# mag_pos.net
KiCad netlist of a schematic drawn in Altium Designer
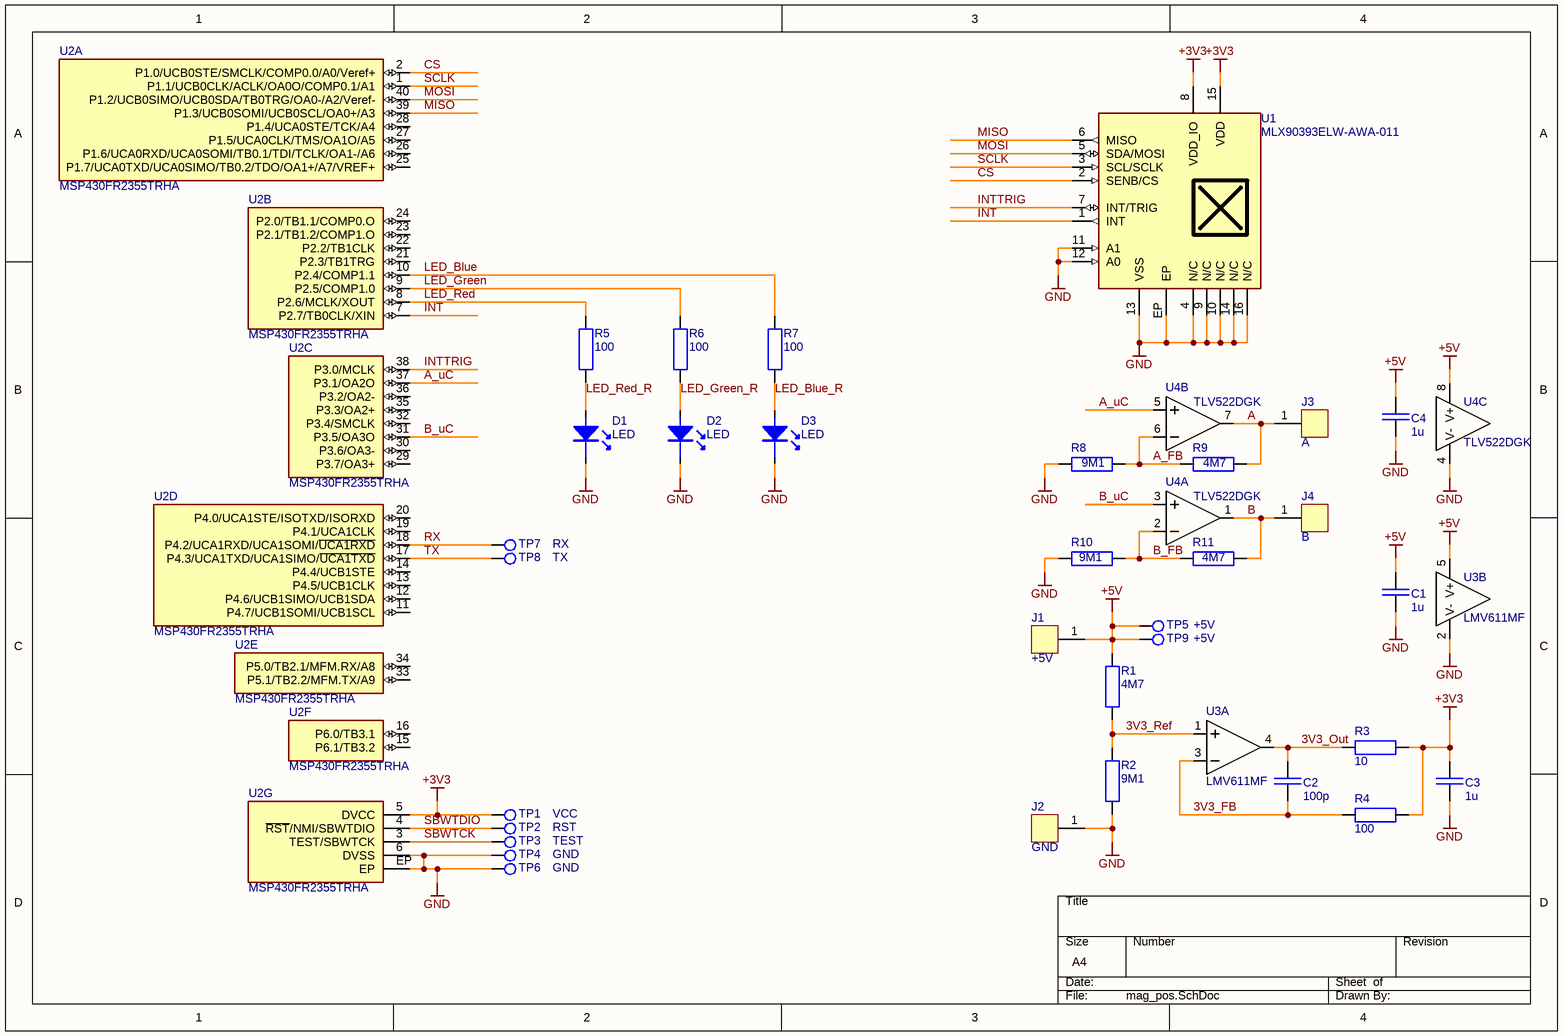
[diagram p0: mag_pos.SchDoc]

(export (version "E")
  (design (tool "Eeschema 10.0.6"))
  (components
    (comp (ref "C1")
      (value "1u")
      (footprint "AHO_Altium_Lib:C_0603_S")
      (libsource (lib "AHO_Altium_Lib") (part "C"))
    )
    (comp (ref "C2")
      (value "100p")
      (footprint "AHO_Altium_Lib:C_0603_S")
      (libsource (lib "AHO_Altium_Lib") (part "C"))
    )
    (comp (ref "C3")
      (value "1u")
      (footprint "AHO_Altium_Lib:C_0603_S")
      (libsource (lib "AHO_Altium_Lib") (part "C"))
    )
    (comp (ref "C4")
      (value "1u")
      (footprint "AHO_Altium_Lib:C_0603_S")
      (libsource (lib "AHO_Altium_Lib") (part "C"))
    )
    (comp (ref "D1")
      (value "LED")
      (footprint "LED_0603_S_RED")
      (libsource (lib "AHO_Altium_Lib") (part "LED"))
    )
    (comp (ref "D2")
      (value "LED")
      (footprint "LED_0603_S_GREEN")
      (libsource (lib "AHO_Altium_Lib") (part "LED"))
    )
    (comp (ref "D3")
      (value "LED")
      (footprint "LED_0603_S_BLUE")
      (libsource (lib "AHO_Altium_Lib") (part "LED"))
    )
    (comp (ref "J1")
      (value "+5V")
      (footprint "mag_pos:WIRE_1MM_1.5MM_THT")
      (description "1mm Wire")
      (libsource (lib "") (part "Wire_1MM_1"))
    )
    (comp (ref "J2")
      (value "GND")
      (footprint "mag_pos:WIRE_1MM_1.5MM_THT")
      (description "1mm Wire")
      (libsource (lib "") (part "Wire_1MM_1"))
    )
    (comp (ref "J3")
      (value "A")
      (footprint "mag_pos:WIRE_1MM_1.5MM_THT")
      (description "1mm Wire")
      (libsource (lib "mag_pos") (part "Wire_1MM"))
    )
    (comp (ref "J4")
      (value "B")
      (footprint "mag_pos:WIRE_1MM_1.5MM_THT")
      (description "1mm Wire")
      (libsource (lib "mag_pos") (part "Wire_1MM"))
    )
    (comp (ref "R1")
      (value "4M7")
      (footprint "AHO_Altium_Lib:R_0603_S")
      (description "Normaler Widerstand")
      (libsource (lib "AHO_Altium_Lib") (part "R"))
    )
    (comp (ref "R2")
      (value "9M1")
      (footprint "AHO_Altium_Lib:R_0603_S")
      (description "Normaler Widerstand")
      (libsource (lib "AHO_Altium_Lib") (part "R"))
    )
    (comp (ref "R3")
      (value "10")
      (footprint "AHO_Altium_Lib:R_0603_S")
      (description "Normaler Widerstand")
      (libsource (lib "AHO_Altium_Lib") (part "R"))
    )
    (comp (ref "R4")
      (value "100")
      (footprint "AHO_Altium_Lib:R_0603_S")
      (description "Normaler Widerstand")
      (libsource (lib "AHO_Altium_Lib") (part "R"))
    )
    (comp (ref "R5")
      (value "100")
      (footprint "AHO_Altium_Lib:R_0603_S")
      (description "Normaler Widerstand")
      (libsource (lib "AHO_Altium_Lib") (part "R"))
    )
    (comp (ref "R6")
      (value "100")
      (footprint "AHO_Altium_Lib:R_0603_S")
      (description "Normaler Widerstand")
      (libsource (lib "AHO_Altium_Lib") (part "R"))
    )
    (comp (ref "R7")
      (value "100")
      (footprint "AHO_Altium_Lib:R_0603_S")
      (description "Normaler Widerstand")
      (libsource (lib "AHO_Altium_Lib") (part "R"))
    )
    (comp (ref "R8")
      (value "9M1")
      (footprint "AHO_Altium_Lib:R_0603_S")
      (description "Normaler Widerstand")
      (libsource (lib "AHO_Altium_Lib") (part "R"))
    )
    (comp (ref "R9")
      (value "4M7")
      (footprint "AHO_Altium_Lib:R_0603_S")
      (description "Normaler Widerstand")
      (libsource (lib "AHO_Altium_Lib") (part "R"))
    )
    (comp (ref "R10")
      (value "9M1")
      (footprint "AHO_Altium_Lib:R_0603_S")
      (description "Normaler Widerstand")
      (libsource (lib "AHO_Altium_Lib") (part "R"))
    )
    (comp (ref "R11")
      (value "4M7")
      (footprint "AHO_Altium_Lib:R_0603_S")
      (description "Normaler Widerstand")
      (libsource (lib "AHO_Altium_Lib") (part "R"))
    )
    (comp (ref "TP1")
      (value "VCC")
      (footprint "mag_pos:TP_SMD_1MM")
      (description "Testpoint SMD 1mm")
      (libsource (lib "mag_pos") (part "TP_SMD_1mm"))
    )
    (comp (ref "TP2")
      (value "RST")
      (footprint "mag_pos:TP_SMD_1MM")
      (description "Testpoint SMD 1mm")
      (libsource (lib "mag_pos") (part "TP_SMD_1mm"))
    )
    (comp (ref "TP3")
      (value "TEST")
      (footprint "mag_pos:TP_SMD_1MM")
      (description "Testpoint SMD 1mm")
      (libsource (lib "mag_pos") (part "TP_SMD_1mm"))
    )
    (comp (ref "TP4")
      (value "GND")
      (footprint "mag_pos:TP_SMD_1MM")
      (description "Testpoint SMD 1mm")
      (libsource (lib "mag_pos") (part "TP_SMD_1mm"))
    )
    (comp (ref "TP5")
      (value "+5V")
      (footprint "mag_pos:TP_SMD_1MM")
      (description "Testpoint SMD 1mm")
      (libsource (lib "mag_pos") (part "TP_SMD_1mm"))
    )
    (comp (ref "TP6")
      (value "GND")
      (footprint "mag_pos:TP_SMD_1MM")
      (description "Testpoint SMD 1mm")
      (libsource (lib "mag_pos") (part "TP_SMD_1mm"))
    )
    (comp (ref "TP7")
      (value "RX")
      (footprint "mag_pos:TP_SMD_1MM")
      (description "Testpoint SMD 1mm")
      (libsource (lib "mag_pos") (part "TP_SMD_1mm"))
    )
    (comp (ref "TP8")
      (value "TX")
      (footprint "mag_pos:TP_SMD_1MM")
      (description "Testpoint SMD 1mm")
      (libsource (lib "mag_pos") (part "TP_SMD_1mm"))
    )
    (comp (ref "TP9")
      (value "+5V")
      (footprint "mag_pos:TP_SMD_1MM")
      (description "Testpoint SMD 1mm")
      (libsource (lib "mag_pos") (part "TP_SMD_1mm"))
    )
    (comp (ref "U1")
      (value "MLX90393ELW-AWA-011")
      (footprint "mag_pos:QFN50P300X300X100-16")
      (description "Triaxis Magnetic Node, QFN16")
      (libsource (lib "mag_pos") (part "MLX90393ELW-AWA-011"))
    )
    (comp (ref "U2")
      (value "MSP430FR2355TRHA")
      (footprint "mag_pos:QFN50P600X600X100-40")
      (description "Mixed-Signal Microcontroller, 16Bit, 32kB FRAM, 4kB SRAM, QFN40")
      (libsource (lib "mag_pos") (part "MSP430FR2355TRHA"))
    )
    (comp (ref "U3")
      (value "LMV611MF")
      (footprint "mag_pos:SOT23-5_1.45")
      (description "LMV611 SOT-23-5 Single, 1.4-MHz, Low-Power, General-Purpose 1.8-V Operational Amplifier")
      (fields (field (name "MANUFACTURER") "TI"))
      (libsource (lib "mag_pos") (part "LMV611MF"))
    )
    (comp (ref "U4")
      (value "TLV522DGK")
      (footprint "mag_pos:SOP65P500X300X110-8")
      (description "TLV522 VSSOP-8 Dual Nanopower, 500nA, RRIO CMOS Operational Amplifier")
      (fields (field (name "MANUFACTURER") "TI"))
      (libsource (lib "mag_pos") (part "TLV522DGK"))
    )
  )
  (nets
    (net (code "1") (name "+3V3") (class "Default")
      (node (ref "C3") (pin "1") (pinfunction "1_1") (pintype "passive"))
      (node (ref "R3") (pin "2") (pintype "passive"))
      (node (ref "R4") (pin "2") (pintype "passive"))
      (node (ref "TP1") (pin "1") (pinfunction "1_1") (pintype "passive"))
      (node (ref "U1") (pin "15") (pinfunction "VDD_15") (pintype "power_in"))
      (node (ref "U1") (pin "8") (pinfunction "VDD_IO_8") (pintype "power_in"))
      (node (ref "U2") (pin "5") (pinfunction "DVCC_5") (pintype "power_in"))
    )
    (net (code "2") (name "+5V") (class "Default")
      (node (ref "C1") (pin "1") (pinfunction "1_1") (pintype "passive"))
      (node (ref "C4") (pin "1") (pinfunction "1_1") (pintype "passive"))
      (node (ref "J1") (pin "1") (pinfunction "1_1") (pintype "passive"))
      (node (ref "R1") (pin "1") (pintype "passive"))
      (node (ref "TP5") (pin "1") (pinfunction "1_1") (pintype "passive"))
      (node (ref "TP9") (pin "1") (pinfunction "1_1") (pintype "passive"))
      (node (ref "U3") (pin "5") (pinfunction "V+_5") (pintype "passive"))
      (node (ref "U4") (pin "8") (pinfunction "V+_8") (pintype "passive"))
    )
    (net (code "3") (name "/3V3_FB") (class "Default")
      (node (ref "C2") (pin "2") (pinfunction "2_2") (pintype "passive"))
      (node (ref "R4") (pin "1") (pintype "passive"))
      (node (ref "U3") (pin "3") (pinfunction "-IN_3") (pintype "passive"))
    )
    (net (code "4") (name "/3V3_Out") (class "Default")
      (node (ref "C2") (pin "1") (pinfunction "1_1") (pintype "passive"))
      (node (ref "R3") (pin "1") (pintype "passive"))
      (node (ref "U3") (pin "4") (pinfunction "4_4") (pintype "passive"))
    )
    (net (code "5") (name "/3V3_Ref") (class "Default")
      (node (ref "R1") (pin "2") (pintype "passive"))
      (node (ref "R2") (pin "1") (pintype "passive"))
      (node (ref "U3") (pin "1") (pinfunction "+IN_1") (pintype "passive"))
    )
    (net (code "6") (name "/A") (class "Default")
      (node (ref "J3") (pin "1") (pinfunction "1_1") (pintype "passive"))
      (node (ref "R9") (pin "1") (pintype "passive"))
      (node (ref "U4") (pin "7") (pinfunction "Out_7") (pintype "passive"))
    )
    (net (code "7") (name "/A_FB") (class "Default")
      (node (ref "R8") (pin "1") (pintype "passive"))
      (node (ref "R9") (pin "2") (pintype "passive"))
      (node (ref "U4") (pin "6") (pinfunction "-IN_6") (pintype "passive"))
    )
    (net (code "8") (name "/A_uC") (class "Default")
      (node (ref "U2") (pin "37") (pinfunction "P3.1/OA2O_37") (pintype "bidirectional"))
      (node (ref "U4") (pin "5") (pinfunction "+IN_5") (pintype "passive"))
    )
    (net (code "9") (name "/B") (class "Default")
      (node (ref "J4") (pin "1") (pinfunction "1_1") (pintype "passive"))
      (node (ref "R11") (pin "1") (pintype "passive"))
      (node (ref "U4") (pin "1") (pinfunction "Out_1") (pintype "passive"))
    )
    (net (code "10") (name "/B_FB") (class "Default")
      (node (ref "R10") (pin "1") (pintype "passive"))
      (node (ref "R11") (pin "2") (pintype "passive"))
      (node (ref "U4") (pin "2") (pinfunction "-IN_2") (pintype "passive"))
    )
    (net (code "11") (name "/B_uC") (class "Default")
      (node (ref "U2") (pin "31") (pinfunction "P3.5/OA3O_31") (pintype "bidirectional"))
      (node (ref "U4") (pin "3") (pinfunction "+IN_3") (pintype "passive"))
    )
    (net (code "12") (name "/CS") (class "Default")
      (node (ref "U1") (pin "2") (pinfunction "SENB/CS_2") (pintype "input"))
      (node (ref "U2") (pin "2") (pinfunction "P1.0/UCB0STE/SMCLK/COMP0.0/A0/Veref+_2") (pintype "bidirectional"))
    )
    (net (code "13") (name "/INT") (class "Default")
      (node (ref "U1") (pin "1") (pinfunction "INT_1") (pintype "output"))
      (node (ref "U2") (pin "7") (pinfunction "P2.7/TB0CLK/XIN_7") (pintype "bidirectional"))
    )
    (net (code "14") (name "/INTTRIG") (class "Default")
      (node (ref "U1") (pin "7") (pinfunction "INT/TRIG_7") (pintype "bidirectional"))
      (node (ref "U2") (pin "38") (pinfunction "P3.0/MCLK_38") (pintype "bidirectional"))
    )
    (net (code "15") (name "/LED_Blue") (class "Default")
      (node (ref "R7") (pin "2") (pintype "passive"))
      (node (ref "U2") (pin "10") (pinfunction "P2.4/COMP1.1_10") (pintype "bidirectional"))
    )
    (net (code "16") (name "/LED_Blue_R") (class "Default")
      (node (ref "D3") (pin "A") (pinfunction "A_A") (pintype "passive"))
      (node (ref "R7") (pin "1") (pintype "passive"))
    )
    (net (code "17") (name "/LED_Green") (class "Default")
      (node (ref "R6") (pin "2") (pintype "passive"))
      (node (ref "U2") (pin "9") (pinfunction "P2.5/COMP1.0_9") (pintype "bidirectional"))
    )
    (net (code "18") (name "/LED_Green_R") (class "Default")
      (node (ref "D2") (pin "A") (pinfunction "A_A") (pintype "passive"))
      (node (ref "R6") (pin "1") (pintype "passive"))
    )
    (net (code "19") (name "/LED_Red") (class "Default")
      (node (ref "R5") (pin "2") (pintype "passive"))
      (node (ref "U2") (pin "8") (pinfunction "P2.6/MCLK/XOUT_8") (pintype "bidirectional"))
    )
    (net (code "20") (name "/LED_Red_R") (class "Default")
      (node (ref "D1") (pin "A") (pinfunction "A_A") (pintype "passive"))
      (node (ref "R5") (pin "1") (pintype "passive"))
    )
    (net (code "21") (name "/MISO") (class "Default")
      (node (ref "U1") (pin "6") (pinfunction "MISO_6") (pintype "output"))
      (node (ref "U2") (pin "39") (pinfunction "P1.3/UCB0SOMI/UCB0SCL/OA0+/A3_39") (pintype "bidirectional"))
    )
    (net (code "22") (name "/MOSI") (class "Default")
      (node (ref "U1") (pin "5") (pinfunction "SDA/MOSI_5") (pintype "bidirectional"))
      (node (ref "U2") (pin "40") (pinfunction "P1.2/UCB0SIMO/UCB0SDA/TB0TRG/OA0-/A2/Veref-_40") (pintype "bidirectional"))
    )
    (net (code "23") (name "/RX") (class "Default")
      (node (ref "TP7") (pin "1") (pinfunction "1_1") (pintype "passive"))
      (node (ref "U2") (pin "18") (pinfunction "P4.2/UCA1RXD/UCA1SOMI/~{UCA1RXD}_18") (pintype "bidirectional"))
    )
    (net (code "24") (name "/SBWTCK") (class "Default")
      (node (ref "TP3") (pin "1") (pinfunction "1_1") (pintype "passive"))
      (node (ref "U2") (pin "3") (pinfunction "TEST/SBWTCK_3") (pintype "power_in"))
    )
    (net (code "25") (name "/SBWTDIO") (class "Default")
      (node (ref "TP2") (pin "1") (pinfunction "1_1") (pintype "passive"))
      (node (ref "U2") (pin "4") (pinfunction "~{RST}/NMI/SBWTDIO_4") (pintype "power_in"))
    )
    (net (code "26") (name "/SCLK") (class "Default")
      (node (ref "U1") (pin "3") (pinfunction "SCL/SCLK_3") (pintype "input"))
      (node (ref "U2") (pin "1") (pinfunction "P1.1/UCB0CLK/ACLK/OA0O/COMP0.1/A1_1") (pintype "bidirectional"))
    )
    (net (code "27") (name "/TX") (class "Default")
      (node (ref "TP8") (pin "1") (pinfunction "1_1") (pintype "passive"))
      (node (ref "U2") (pin "17") (pinfunction "P4.3/UCA1TXD/UCA1SIMO/~{UCA1TXD}_17") (pintype "bidirectional"))
    )
    (net (code "28") (name "GND") (class "Default")
      (node (ref "C1") (pin "2") (pinfunction "2_2") (pintype "passive"))
      (node (ref "C3") (pin "2") (pinfunction "2_2") (pintype "passive"))
      (node (ref "C4") (pin "2") (pinfunction "2_2") (pintype "passive"))
      (node (ref "D1") (pin "K") (pinfunction "K_K") (pintype "passive"))
      (node (ref "D2") (pin "K") (pinfunction "K_K") (pintype "passive"))
      (node (ref "D3") (pin "K") (pinfunction "K_K") (pintype "passive"))
      (node (ref "J2") (pin "1") (pinfunction "1_1") (pintype "passive"))
      (node (ref "R10") (pin "2") (pintype "passive"))
      (node (ref "R2") (pin "2") (pintype "passive"))
      (node (ref "R8") (pin "2") (pintype "passive"))
      (node (ref "TP4") (pin "1") (pinfunction "1_1") (pintype "passive"))
      (node (ref "TP6") (pin "1") (pinfunction "1_1") (pintype "passive"))
      (node (ref "U1") (pin "10") (pinfunction "N/C_10") (pintype "passive"))
      (node (ref "U1") (pin "11") (pinfunction "A1_11") (pintype "input"))
      (node (ref "U1") (pin "12") (pinfunction "A0_12") (pintype "input"))
      (node (ref "U1") (pin "13") (pinfunction "VSS_13") (pintype "power_in"))
      (node (ref "U1") (pin "14") (pinfunction "N/C_14") (pintype "passive"))
      (node (ref "U1") (pin "16") (pinfunction "N/C_16") (pintype "passive"))
      (node (ref "U1") (pin "4") (pinfunction "N/C_4") (pintype "passive"))
      (node (ref "U1") (pin "9") (pinfunction "N/C_9") (pintype "passive"))
      (node (ref "U1") (pin "EP") (pinfunction "EP_EP") (pintype "passive"))
      (node (ref "U2") (pin "6") (pinfunction "DVSS_6") (pintype "power_in"))
      (node (ref "U2") (pin "EP") (pinfunction "EP_EP") (pintype "power_in"))
      (node (ref "U3") (pin "2") (pinfunction "V-_2") (pintype "passive"))
      (node (ref "U4") (pin "4") (pinfunction "V-_4") (pintype "passive"))
    )
    (net (code "29") (name "unconnected-(U2A-P1.4{slash}UCA0STE{slash}TCK{slash}A4-Pad28)") (class "Default")
      (node (ref "U2") (pin "28") (pinfunction "P1.4/UCA0STE/TCK/A4_28") (pintype "bidirectional"))
    )
    (net (code "30") (name "unconnected-(U2A-P1.5{slash}UCA0CLK{slash}TMS{slash}OA1O{slash}A5-Pad27)") (class "Default")
      (node (ref "U2") (pin "27") (pinfunction "P1.5/UCA0CLK/TMS/OA1O/A5_27") (pintype "bidirectional"))
    )
    (net (code "31") (name "unconnected-(U2A-P1.6{slash}UCA0RXD{slash}UCA0SOMI{slash}TB0.1{slash}TDI{slash}TCLK{slash}OA1-{slash}A6-Pad26)") (class "Default")
      (node (ref "U2") (pin "26") (pinfunction "P1.6/UCA0RXD/UCA0SOMI/TB0.1/TDI/TCLK/OA1-/A6_26") (pintype "bidirectional"))
    )
    (net (code "32") (name "unconnected-(U2A-P1.7{slash}UCA0TXD{slash}UCA0SIMO{slash}TB0.2{slash}TDO{slash}OA1+{slash}A7{slash}VREF+-Pad25)") (class "Default")
      (node (ref "U2") (pin "25") (pinfunction "P1.7/UCA0TXD/UCA0SIMO/TB0.2/TDO/OA1+/A7/VREF+_25") (pintype "bidirectional"))
    )
    (net (code "33") (name "unconnected-(U2B-P2.0{slash}TB1.1{slash}COMP0.O-Pad24)") (class "Default")
      (node (ref "U2") (pin "24") (pinfunction "P2.0/TB1.1/COMP0.O_24") (pintype "bidirectional"))
    )
    (net (code "34") (name "unconnected-(U2B-P2.1{slash}TB1.2{slash}COMP1.O-Pad23)") (class "Default")
      (node (ref "U2") (pin "23") (pinfunction "P2.1/TB1.2/COMP1.O_23") (pintype "bidirectional"))
    )
    (net (code "35") (name "unconnected-(U2B-P2.2{slash}TB1CLK-Pad22)") (class "Default")
      (node (ref "U2") (pin "22") (pinfunction "P2.2/TB1CLK_22") (pintype "bidirectional"))
    )
    (net (code "36") (name "unconnected-(U2B-P2.3{slash}TB1TRG-Pad21)") (class "Default")
      (node (ref "U2") (pin "21") (pinfunction "P2.3/TB1TRG_21") (pintype "bidirectional"))
    )
    (net (code "37") (name "unconnected-(U2C-P3.2{slash}OA2--Pad36)") (class "Default")
      (node (ref "U2") (pin "36") (pinfunction "P3.2/OA2-_36") (pintype "bidirectional"))
    )
    (net (code "38") (name "unconnected-(U2C-P3.3{slash}OA2+-Pad35)") (class "Default")
      (node (ref "U2") (pin "35") (pinfunction "P3.3/OA2+_35") (pintype "bidirectional"))
    )
    (net (code "39") (name "unconnected-(U2C-P3.4{slash}SMCLK-Pad32)") (class "Default")
      (node (ref "U2") (pin "32") (pinfunction "P3.4/SMCLK_32") (pintype "bidirectional"))
    )
    (net (code "40") (name "unconnected-(U2C-P3.6{slash}OA3--Pad30)") (class "Default")
      (node (ref "U2") (pin "30") (pinfunction "P3.6/OA3-_30") (pintype "bidirectional"))
    )
    (net (code "41") (name "unconnected-(U2C-P3.7{slash}OA3+-Pad29)") (class "Default")
      (node (ref "U2") (pin "29") (pinfunction "P3.7/OA3+_29") (pintype "bidirectional"))
    )
    (net (code "42") (name "unconnected-(U2D-P4.0{slash}UCA1STE{slash}ISOTXD{slash}ISORXD-Pad20)") (class "Default")
      (node (ref "U2") (pin "20") (pinfunction "P4.0/UCA1STE/ISOTXD/ISORXD_20") (pintype "bidirectional"))
    )
    (net (code "43") (name "unconnected-(U2D-P4.1{slash}UCA1CLK-Pad19)") (class "Default")
      (node (ref "U2") (pin "19") (pinfunction "P4.1/UCA1CLK_19") (pintype "bidirectional"))
    )
    (net (code "44") (name "unconnected-(U2D-P4.4{slash}UCB1STE-Pad14)") (class "Default")
      (node (ref "U2") (pin "14") (pinfunction "P4.4/UCB1STE_14") (pintype "bidirectional"))
    )
    (net (code "45") (name "unconnected-(U2D-P4.5{slash}UCB1CLK-Pad13)") (class "Default")
      (node (ref "U2") (pin "13") (pinfunction "P4.5/UCB1CLK_13") (pintype "bidirectional"))
    )
    (net (code "46") (name "unconnected-(U2D-P4.6{slash}UCB1SIMO{slash}UCB1SDA-Pad12)") (class "Default")
      (node (ref "U2") (pin "12") (pinfunction "P4.6/UCB1SIMO/UCB1SDA_12") (pintype "bidirectional"))
    )
    (net (code "47") (name "unconnected-(U2D-P4.7{slash}UCB1SOMI{slash}UCB1SCL-Pad11)") (class "Default")
      (node (ref "U2") (pin "11") (pinfunction "P4.7/UCB1SOMI/UCB1SCL_11") (pintype "bidirectional"))
    )
    (net (code "48") (name "unconnected-(U2E-P5.0{slash}TB2.1{slash}MFM.RX{slash}A8-Pad34)") (class "Default")
      (node (ref "U2") (pin "34") (pinfunction "P5.0/TB2.1/MFM.RX/A8_34") (pintype "bidirectional"))
    )
    (net (code "49") (name "unconnected-(U2E-P5.1{slash}TB2.2{slash}MFM.TX{slash}A9-Pad33)") (class "Default")
      (node (ref "U2") (pin "33") (pinfunction "P5.1/TB2.2/MFM.TX/A9_33") (pintype "bidirectional"))
    )
    (net (code "50") (name "unconnected-(U2F-P6.0{slash}TB3.1-Pad16)") (class "Default")
      (node (ref "U2") (pin "16") (pinfunction "P6.0/TB3.1_16") (pintype "bidirectional"))
    )
    (net (code "51") (name "unconnected-(U2F-P6.1{slash}TB3.2-Pad15)") (class "Default")
      (node (ref "U2") (pin "15") (pinfunction "P6.1/TB3.2_15") (pintype "bidirectional"))
    )
  )
)
